# Sensors.net
KiCad netlist of a schematic drawn in Altium Designer
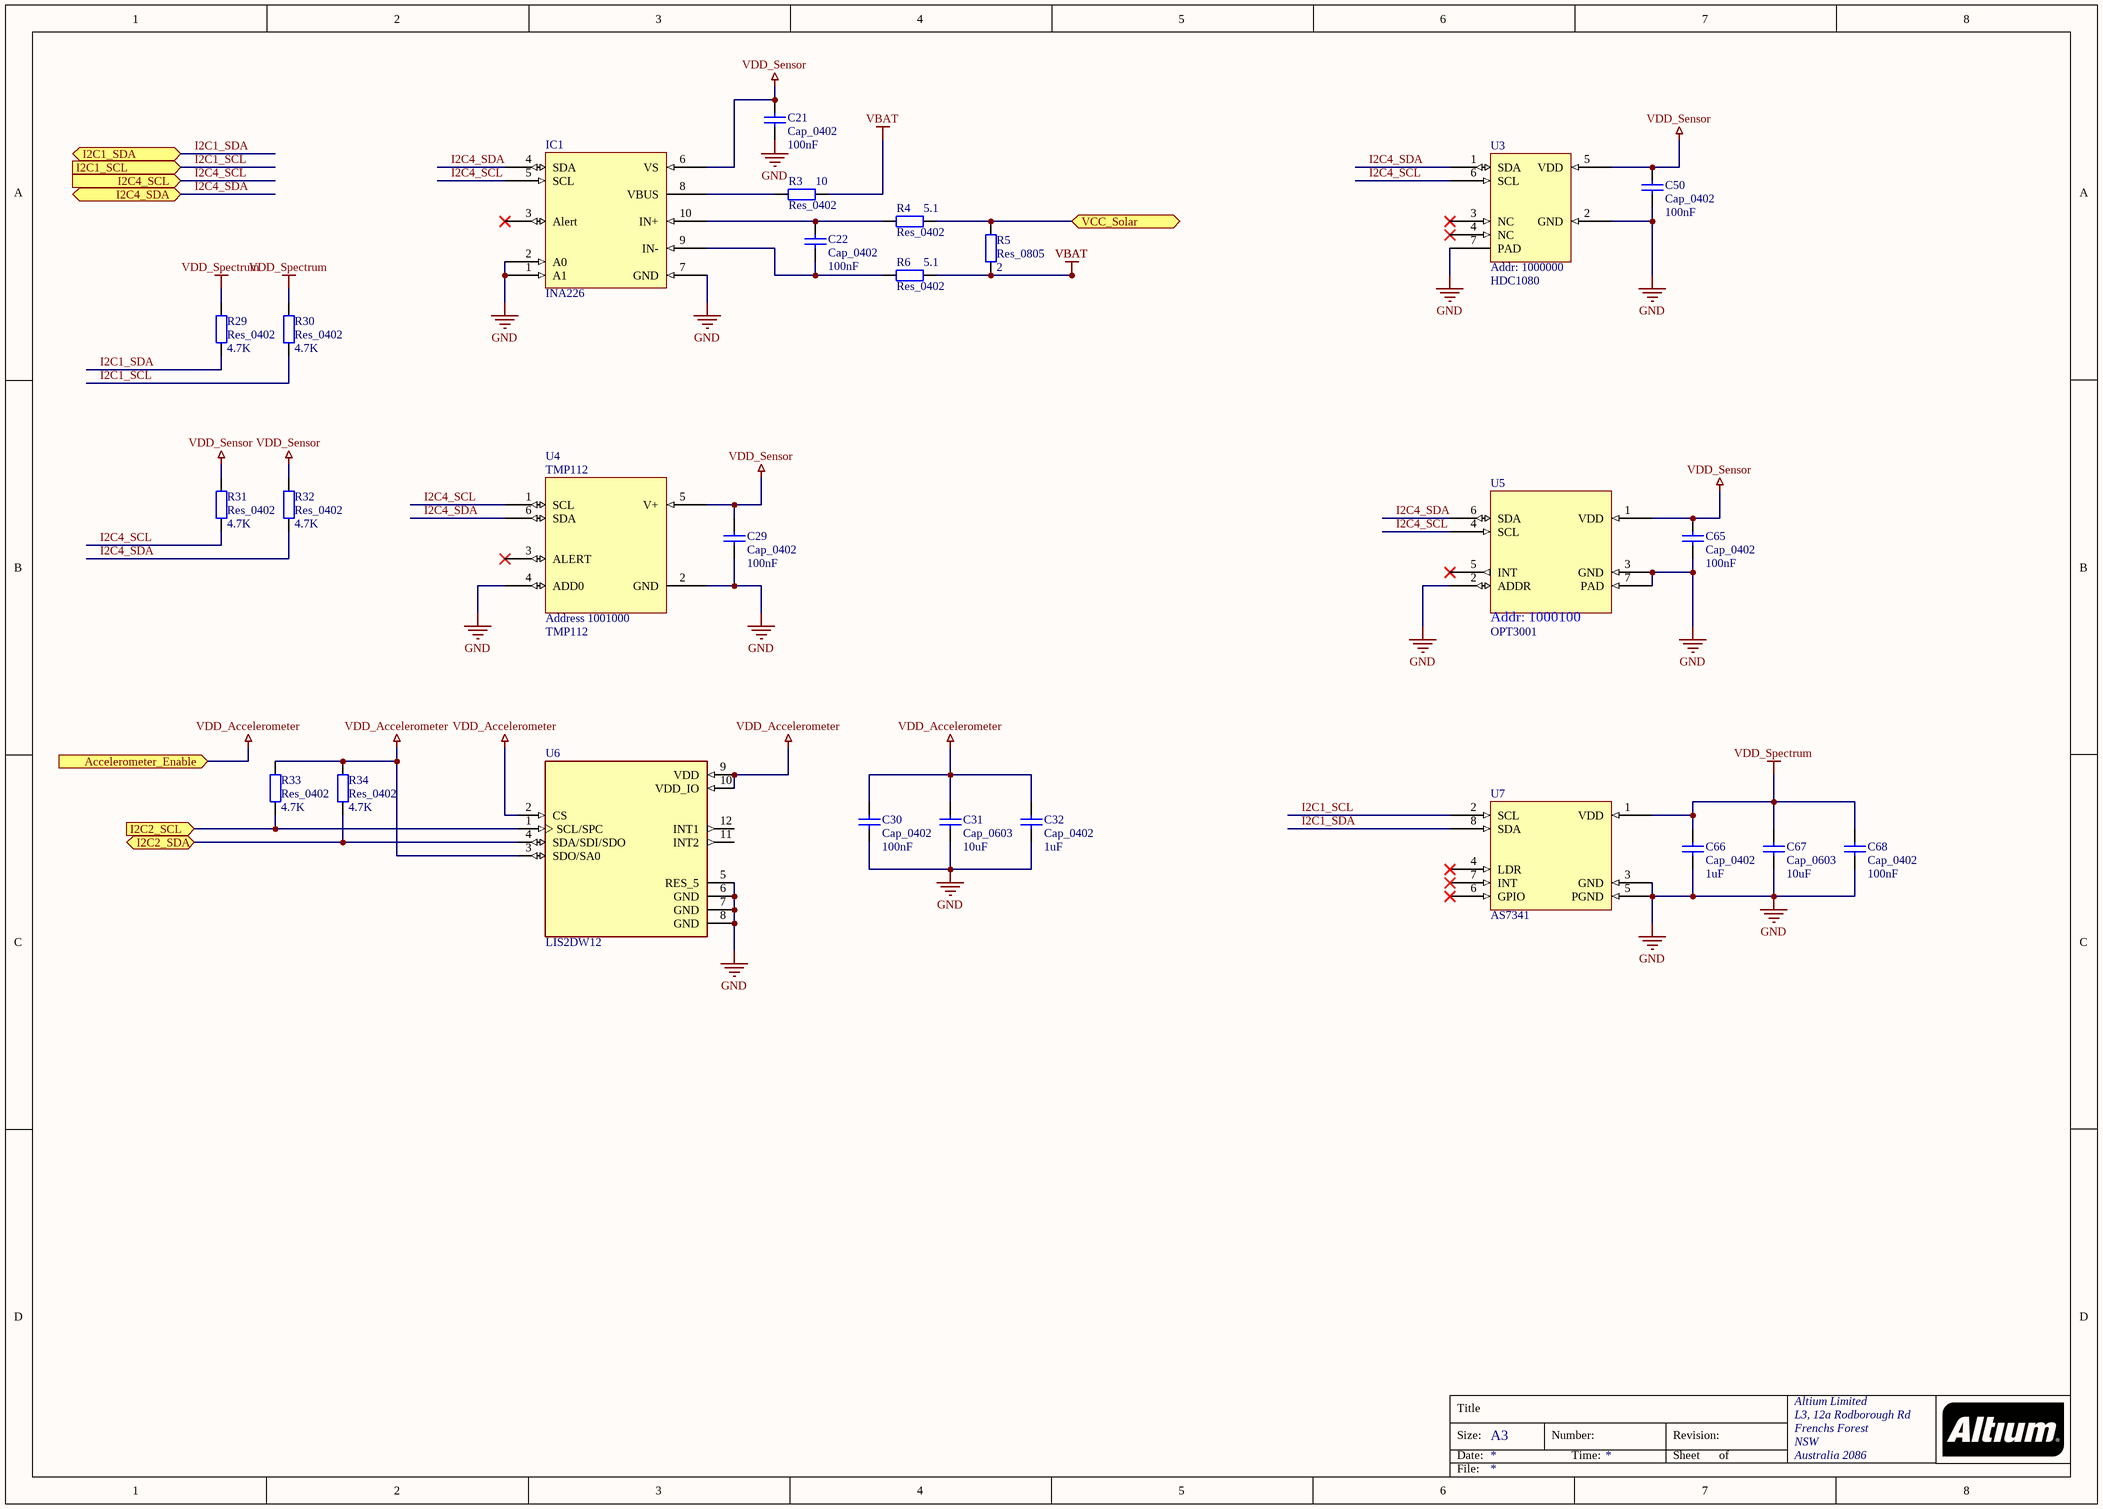
[diagram p0: Sensors.SchDoc]

(export (version "E")
  (design (tool "Eeschema 10.0.6"))
  (components
    (comp (ref "C21")
      (value "Cap_0402")
      (footprint "0402")
      (description "Capacitor")
      (fields (field (name "ALTIUM_VALUE") "100nF") (field (name "PUBLISHER") "Altium Limited"))
      (libsource (lib "Schematic_Components") (part "Cap_0402"))
    )
    (comp (ref "C22")
      (value "Cap_0402")
      (footprint "0402")
      (description "Capacitor")
      (fields (field (name "ALTIUM_VALUE") "100nF") (field (name "PUBLISHER") "Altium Limited"))
      (libsource (lib "Schematic_Components") (part "Cap_0402"))
    )
    (comp (ref "C29")
      (value "Cap_0402")
      (footprint "0402")
      (description "Capacitor")
      (fields (field (name "ALTIUM_VALUE") "100nF") (field (name "PUBLISHER") "Altium Limited"))
      (libsource (lib "Schematic_Components") (part "Cap_0402"))
    )
    (comp (ref "C30")
      (value "Cap_0402")
      (footprint "0402")
      (description "Capacitor")
      (fields (field (name "ALTIUM_VALUE") "100nF") (field (name "PUBLISHER") "Altium Limited"))
      (libsource (lib "Schematic_Components") (part "Cap_0402"))
    )
    (comp (ref "C31")
      (value "Cap_0603")
      (footprint "0603")
      (description "Capacitor")
      (fields (field (name "ALTIUM_VALUE") "10uF") (field (name "PUBLISHER") "Altium Limited"))
      (libsource (lib "Schematic_Components") (part "Cap_0603"))
    )
    (comp (ref "C32")
      (value "Cap_0402")
      (footprint "0402")
      (description "Capacitor")
      (fields (field (name "ALTIUM_VALUE") "1uF") (field (name "PUBLISHER") "Altium Limited"))
      (libsource (lib "Schematic_Components") (part "Cap_0402"))
    )
    (comp (ref "C50")
      (value "Cap_0402")
      (footprint "0402")
      (description "Capacitor")
      (fields (field (name "ALTIUM_VALUE") "100nF") (field (name "PUBLISHER") "Altium Limited"))
      (libsource (lib "Schematic_Components") (part "Cap_0402"))
    )
    (comp (ref "C65")
      (value "Cap_0402")
      (footprint "0402")
      (description "Capacitor")
      (fields (field (name "ALTIUM_VALUE") "100nF") (field (name "PUBLISHER") "Altium Limited"))
      (libsource (lib "Schematic_Components") (part "Cap_0402"))
    )
    (comp (ref "C66")
      (value "Cap_0402")
      (footprint "0402")
      (description "Capacitor")
      (fields (field (name "ALTIUM_VALUE") "1uF") (field (name "PUBLISHER") "Altium Limited"))
      (libsource (lib "Schematic_Components") (part "Cap_0402"))
    )
    (comp (ref "C67")
      (value "Cap_0603")
      (footprint "0603")
      (description "Capacitor")
      (fields (field (name "ALTIUM_VALUE") "10uF") (field (name "PUBLISHER") "Altium Limited"))
      (libsource (lib "Schematic_Components") (part "Cap_0603"))
    )
    (comp (ref "C68")
      (value "Cap_0402")
      (footprint "0402")
      (description "Capacitor")
      (fields (field (name "ALTIUM_VALUE") "100nF") (field (name "PUBLISHER") "Altium Limited"))
      (libsource (lib "Schematic_Components") (part "Cap_0402"))
    )
    (comp (ref "IC1")
      (value "INA226")
      (footprint "VSSOP-10")
      (description "Bi-Directional Current and Power Monitor")
      (libsource (lib "Schematic_Components") (part "INA226"))
    )
    (comp (ref "R3")
      (value "Res_0402")
      (footprint "0402")
      (description "Resistor")
      (fields (field (name "ALTIUM_VALUE") "10") (field (name "PUBLISHER") "Altium Limited"))
      (libsource (lib "") (part "Res_0402_1"))
    )
    (comp (ref "R4")
      (value "Res_0402")
      (footprint "0402")
      (description "Resistor")
      (fields (field (name "ALTIUM_VALUE") "5.1") (field (name "PUBLISHER") "Altium Limited"))
      (libsource (lib "") (part "Res_0402_1"))
    )
    (comp (ref "R5")
      (value "Res_0805")
      (footprint "0805")
      (description "Resistor")
      (fields (field (name "ALTIUM_VALUE") "2") (field (name "PUBLISHER") "Altium Limited"))
      (libsource (lib "Schematic_Components") (part "Res_0805"))
    )
    (comp (ref "R6")
      (value "Res_0402")
      (footprint "0402")
      (description "Resistor")
      (fields (field (name "ALTIUM_VALUE") "5.1") (field (name "PUBLISHER") "Altium Limited"))
      (libsource (lib "") (part "Res_0402_1"))
    )
    (comp (ref "R29")
      (value "Res_0402")
      (footprint "0402")
      (description "Resistor")
      (fields (field (name "ALTIUM_VALUE") "4.7K") (field (name "PUBLISHER") "Altium Limited"))
      (libsource (lib "Schematic_Components") (part "Res_0402"))
    )
    (comp (ref "R30")
      (value "Res_0402")
      (footprint "0402")
      (description "Resistor")
      (fields (field (name "ALTIUM_VALUE") "4.7K") (field (name "PUBLISHER") "Altium Limited"))
      (libsource (lib "Schematic_Components") (part "Res_0402"))
    )
    (comp (ref "R31")
      (value "Res_0402")
      (footprint "0402")
      (description "Resistor")
      (fields (field (name "ALTIUM_VALUE") "4.7K") (field (name "PUBLISHER") "Altium Limited"))
      (libsource (lib "Schematic_Components") (part "Res_0402"))
    )
    (comp (ref "R32")
      (value "Res_0402")
      (footprint "0402")
      (description "Resistor")
      (fields (field (name "ALTIUM_VALUE") "4.7K") (field (name "PUBLISHER") "Altium Limited"))
      (libsource (lib "Schematic_Components") (part "Res_0402"))
    )
    (comp (ref "R33")
      (value "Res_0402")
      (footprint "0402")
      (description "Resistor")
      (fields (field (name "ALTIUM_VALUE") "4.7K") (field (name "PUBLISHER") "Altium Limited"))
      (libsource (lib "Schematic_Components") (part "Res_0402"))
    )
    (comp (ref "R34")
      (value "Res_0402")
      (footprint "0402")
      (description "Resistor")
      (fields (field (name "ALTIUM_VALUE") "4.7K") (field (name "PUBLISHER") "Altium Limited"))
      (libsource (lib "Schematic_Components") (part "Res_0402"))
    )
    (comp (ref "U3")
      (value "HDC1080")
      (footprint "PSON95P300X80_HS")
      (description "Humidity Sensor")
      (libsource (lib "Schematic_Components") (part "HDC1080"))
    )
    (comp (ref "U4")
      (value "TMP112")
      (footprint "SOT563 (6)")
      (description "Temperature measurement unit")
      (fields (field (name "MAN. PART NO.") "TMP112AIDRLR"))
      (libsource (lib "Schematic_Components") (part "TMP112"))
    )
    (comp (ref "U5")
      (value "OPT3001")
      (footprint "USON-6")
      (description "Lux sensor")
      (libsource (lib "Schematic_Components") (part "OPT3001"))
    )
    (comp (ref "U6")
      (value "LIS2DW12")
      (footprint "LGA-12")
      (description "Accelerometer X, Y, Z Axis Â±2g, 4g, 8g, 16g 0.5Hz ~ 672Hz 12-LGA _2x2_")
      (fields (field (name "MF") "STMicroelectronics") (field (name "MP") "LIS2DH12"))
      (libsource (lib "Schematic_Components") (part "LIS2DW12"))
    )
    (comp (ref "U7")
      (value "AS7341")
      (footprint "OLGA-8")
      (description "Spectrum Sensor")
      (libsource (lib "Schematic_Components") (part "AS7341"))
    )
  )
  (nets
    (net (code "1") (name "/I2C1_SCL") (class "Default")
      (node (ref "R30") (pin "1") (pinfunction "1_1") (pintype "passive"))
      (node (ref "U7") (pin "2") (pinfunction "SCL_2") (pintype "input"))
    )
    (net (code "2") (name "/I2C1_SDA") (class "Default")
      (node (ref "R29") (pin "1") (pinfunction "1_1") (pintype "passive"))
      (node (ref "U7") (pin "8") (pinfunction "SDA_8") (pintype "input"))
    )
    (net (code "3") (name "/I2C2_SCL") (class "Default")
      (node (ref "R33") (pin "1") (pinfunction "1_1") (pintype "passive"))
      (node (ref "U6") (pin "1") (pinfunction "SCL/SPC_1") (pintype "input"))
    )
    (net (code "4") (name "/I2C2_SDA") (class "Default")
      (node (ref "R34") (pin "1") (pinfunction "1_1") (pintype "passive"))
      (node (ref "U6") (pin "4") (pinfunction "SDA/SDI/SDO_4") (pintype "bidirectional"))
    )
    (net (code "5") (name "/I2C4_SCL") (class "Default")
      (node (ref "IC1") (pin "5") (pinfunction "SCL_5") (pintype "input"))
      (node (ref "R31") (pin "1") (pinfunction "1_1") (pintype "passive"))
      (node (ref "U3") (pin "6") (pinfunction "SCL_6") (pintype "input"))
      (node (ref "U4") (pin "1") (pinfunction "SCL_1") (pintype "bidirectional"))
      (node (ref "U5") (pin "4") (pinfunction "SCL_4") (pintype "input"))
    )
    (net (code "6") (name "/I2C4_SDA") (class "Default")
      (node (ref "IC1") (pin "4") (pinfunction "SDA_4") (pintype "bidirectional"))
      (node (ref "R32") (pin "1") (pinfunction "1_1") (pintype "passive"))
      (node (ref "U3") (pin "1") (pinfunction "SDA_1") (pintype "bidirectional"))
      (node (ref "U4") (pin "6") (pinfunction "SDA_6") (pintype "bidirectional"))
      (node (ref "U5") (pin "6") (pinfunction "SDA_6") (pintype "bidirectional"))
    )
    (net (code "7") (name "/VCC_Solar") (class "Default")
      (node (ref "R4") (pin "2") (pinfunction "2_2") (pintype "passive"))
      (node (ref "R5") (pin "2") (pinfunction "2_2") (pintype "passive"))
    )
    (net (code "8") (name "GND") (class "Default")
      (node (ref "C21") (pin "1") (pinfunction "1_1") (pintype "passive"))
      (node (ref "C29") (pin "1") (pinfunction "1_1") (pintype "passive"))
      (node (ref "C30") (pin "1") (pinfunction "1_1") (pintype "passive"))
      (node (ref "C31") (pin "1") (pinfunction "1_1") (pintype "passive"))
      (node (ref "C32") (pin "1") (pinfunction "1_1") (pintype "passive"))
      (node (ref "C50") (pin "1") (pinfunction "1_1") (pintype "passive"))
      (node (ref "C65") (pin "1") (pinfunction "1_1") (pintype "passive"))
      (node (ref "C66") (pin "1") (pinfunction "1_1") (pintype "passive"))
      (node (ref "C67") (pin "1") (pinfunction "1_1") (pintype "passive"))
      (node (ref "C68") (pin "1") (pinfunction "1_1") (pintype "passive"))
      (node (ref "IC1") (pin "1") (pinfunction "A1_1") (pintype "input"))
      (node (ref "IC1") (pin "2") (pinfunction "A0_2") (pintype "input"))
      (node (ref "IC1") (pin "7") (pinfunction "GND_7") (pintype "input"))
      (node (ref "U3") (pin "2") (pinfunction "GND_2") (pintype "input"))
      (node (ref "U3") (pin "7") (pinfunction "PAD_7") (pintype "passive"))
      (node (ref "U4") (pin "2") (pinfunction "GND_2") (pintype "passive"))
      (node (ref "U4") (pin "4") (pinfunction "ADD0_4") (pintype "bidirectional"))
      (node (ref "U5") (pin "2") (pinfunction "ADDR_2") (pintype "bidirectional"))
      (node (ref "U5") (pin "3") (pinfunction "GND_3") (pintype "input"))
      (node (ref "U5") (pin "7") (pinfunction "PAD_7") (pintype "input"))
      (node (ref "U6") (pin "5") (pinfunction "RES_5_5") (pintype "power_in"))
      (node (ref "U6") (pin "6") (pinfunction "GND_6") (pintype "power_in"))
      (node (ref "U6") (pin "7") (pinfunction "GND_7") (pintype "power_in"))
      (node (ref "U6") (pin "8") (pinfunction "GND_8") (pintype "power_in"))
      (node (ref "U7") (pin "3") (pinfunction "GND_3") (pintype "input"))
      (node (ref "U7") (pin "5") (pinfunction "PGND_5") (pintype "input"))
    )
    (net (code "9") (name "Net-(IC1-IN+)") (class "Default")
      (node (ref "C22") (pin "2") (pinfunction "2_2") (pintype "passive"))
      (node (ref "IC1") (pin "10") (pinfunction "IN+_10") (pintype "input"))
      (node (ref "R4") (pin "1") (pinfunction "1_1") (pintype "passive"))
    )
    (net (code "10") (name "Net-(IC1-IN-)") (class "Default")
      (node (ref "C22") (pin "1") (pinfunction "1_1") (pintype "passive"))
      (node (ref "IC1") (pin "9") (pinfunction "IN-_9") (pintype "input"))
      (node (ref "R6") (pin "1") (pinfunction "1_1") (pintype "passive"))
    )
    (net (code "11") (name "Net-(IC1-VBUS)") (class "Default")
      (node (ref "IC1") (pin "8") (pinfunction "VBUS_8") (pintype "power_in"))
      (node (ref "R3") (pin "1") (pinfunction "1_1") (pintype "passive"))
    )
    (net (code "12") (name "VBAT") (class "Default")
      (node (ref "R3") (pin "2") (pinfunction "2_2") (pintype "passive"))
      (node (ref "R5") (pin "1") (pinfunction "1_1") (pintype "passive"))
      (node (ref "R6") (pin "2") (pinfunction "2_2") (pintype "passive"))
    )
    (net (code "13") (name "VDD_Accelerometer") (class "Default")
      (node (ref "C30") (pin "2") (pinfunction "2_2") (pintype "passive"))
      (node (ref "C31") (pin "2") (pinfunction "2_2") (pintype "passive"))
      (node (ref "C32") (pin "2") (pinfunction "2_2") (pintype "passive"))
      (node (ref "R33") (pin "2") (pinfunction "2_2") (pintype "passive"))
      (node (ref "R34") (pin "2") (pinfunction "2_2") (pintype "passive"))
      (node (ref "U6") (pin "10") (pinfunction "VDD_IO_10") (pintype "input"))
      (node (ref "U6") (pin "2") (pinfunction "CS_2") (pintype "input"))
      (node (ref "U6") (pin "3") (pinfunction "SDO/SA0_3") (pintype "bidirectional"))
      (node (ref "U6") (pin "9") (pinfunction "VDD_9") (pintype "input"))
    )
    (net (code "14") (name "VDD_Sensor") (class "Default")
      (node (ref "C21") (pin "2") (pinfunction "2_2") (pintype "passive"))
      (node (ref "C29") (pin "2") (pinfunction "2_2") (pintype "passive"))
      (node (ref "C50") (pin "2") (pinfunction "2_2") (pintype "passive"))
      (node (ref "C65") (pin "2") (pinfunction "2_2") (pintype "passive"))
      (node (ref "IC1") (pin "6") (pinfunction "VS_6") (pintype "input"))
      (node (ref "R31") (pin "2") (pinfunction "2_2") (pintype "passive"))
      (node (ref "R32") (pin "2") (pinfunction "2_2") (pintype "passive"))
      (node (ref "U3") (pin "5") (pinfunction "VDD_5") (pintype "input"))
      (node (ref "U4") (pin "5") (pinfunction "V+_5") (pintype "input"))
      (node (ref "U5") (pin "1") (pinfunction "VDD_1") (pintype "input"))
    )
    (net (code "15") (name "VDD_Spectrum") (class "Default")
      (node (ref "C66") (pin "2") (pinfunction "2_2") (pintype "passive"))
      (node (ref "C67") (pin "2") (pinfunction "2_2") (pintype "passive"))
      (node (ref "C68") (pin "2") (pinfunction "2_2") (pintype "passive"))
      (node (ref "R29") (pin "2") (pinfunction "2_2") (pintype "passive"))
      (node (ref "R30") (pin "2") (pinfunction "2_2") (pintype "passive"))
      (node (ref "U7") (pin "1") (pinfunction "VDD_1") (pintype "input"))
    )
    (net (code "16") (name "unconnected-(IC1-Alert-Pad3)") (class "Default")
      (node (ref "IC1") (pin "3") (pinfunction "Alert_3") (pintype "bidirectional+no_connect"))
    )
    (net (code "17") (name "unconnected-(U3-NC-Pad3)") (class "Default")
      (node (ref "U3") (pin "3") (pinfunction "NC_3") (pintype "input+no_connect"))
    )
    (net (code "18") (name "unconnected-(U3-NC-Pad4)") (class "Default")
      (node (ref "U3") (pin "4") (pinfunction "NC_4") (pintype "input+no_connect"))
    )
    (net (code "19") (name "unconnected-(U4-ALERT-Pad3)") (class "Default")
      (node (ref "U4") (pin "3") (pinfunction "ALERT_3") (pintype "bidirectional+no_connect"))
    )
    (net (code "20") (name "unconnected-(U5-INT-Pad5)") (class "Default")
      (node (ref "U5") (pin "5") (pinfunction "INT_5") (pintype "output+no_connect"))
    )
    (net (code "21") (name "unconnected-(U6-INT1-Pad12)") (class "Default")
      (node (ref "U6") (pin "12") (pinfunction "INT1_12") (pintype "output"))
    )
    (net (code "22") (name "unconnected-(U6-INT2-Pad11)") (class "Default")
      (node (ref "U6") (pin "11") (pinfunction "INT2_11") (pintype "output"))
    )
    (net (code "23") (name "unconnected-(U7-GPIO-Pad6)") (class "Default")
      (node (ref "U7") (pin "6") (pinfunction "GPIO_6") (pintype "input+no_connect"))
    )
    (net (code "24") (name "unconnected-(U7-INT-Pad7)") (class "Default")
      (node (ref "U7") (pin "7") (pinfunction "INT_7") (pintype "input+no_connect"))
    )
    (net (code "25") (name "unconnected-(U7-LDR-Pad4)") (class "Default")
      (node (ref "U7") (pin "4") (pinfunction "LDR_4") (pintype "input+no_connect"))
    )
  )
)
